# Sheet3.net
KiCad netlist of a schematic drawn in Altium Designer
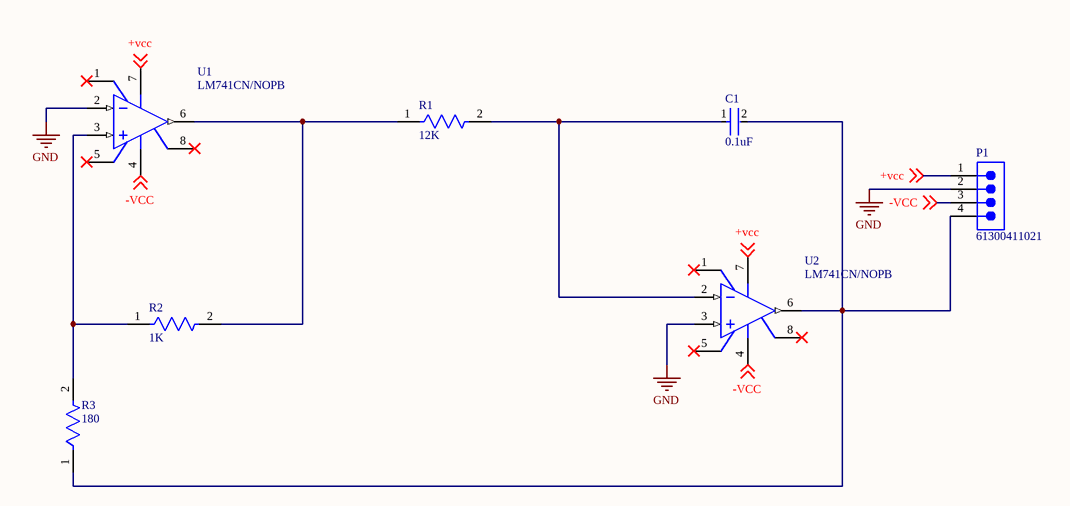
[diagram p0: Sheet3.SchDoc]

(export (version "E")
  (design (tool "Eeschema 10.0.6"))
  (components
    (comp (ref "C1")
      (value "0.1uF")
      (footprint "FP-RDE0M1-MFG")
      (description "Ceramic Capacitor 100nF ±10% 50V X7R Radial")
      (fields (field (name "TOLERANCE") "10%"))
      (libsource (lib "Altium Content Vault") (part "b4654b650e69147ec39a6b967a45e02"))
    )
    (comp (ref "P1")
      (value "61300411021")
      (footprint "61300411021")
      (libsource (lib "Altium Content Vault") (part "Header_Male_1R_04P"))
    )
    (comp (ref "R1")
      (value "12K")
      (footprint "FP-MRS25-MFG")
      (description "RES 1K OHM 0.6W 1% AXIAL")
      (fields (field (name "TOLERANCE") "1%"))
      (libsource (lib "Altium Content Vault") (part "1029c3af85768c4190bb7ad29bc67b5"))
    )
    (comp (ref "R2")
      (value "1K")
      (footprint "FP-MRS25-MFG")
      (description "RES 1K OHM 0.6W 1% AXIAL")
      (fields (field (name "TOLERANCE") "1%"))
      (libsource (lib "Altium Content Vault") (part "1029c3af85768c4190bb7ad29bc67b5"))
    )
    (comp (ref "R3")
      (value "180")
      (footprint "FP-MRS25-MFG")
      (description "RES 1K OHM 0.6W 1% AXIAL")
      (fields (field (name "TOLERANCE") "1%"))
      (libsource (lib "Altium Content Vault") (part "1029c3af85768c4190bb7ad29bc67b5"))
    )
    (comp (ref "U1")
      (value "LM741CN/NOPB")
      (footprint "P0008A")
      (description "Operational Amplifier, 8-pin MDIP, Pb-Free")
      (fields (field (name "MANUFACTURER") "Texas Instruments"))
      (libsource (lib "Altium Content Vault") (part "AMP-OPA-LM741-8"))
    )
    (comp (ref "U2")
      (value "LM741CN/NOPB")
      (footprint "P0008A")
      (description "Operational Amplifier, 8-pin MDIP, Pb-Free")
      (fields (field (name "MANUFACTURER") "Texas Instruments"))
      (libsource (lib "Altium Content Vault") (part "AMP-OPA-LM741-8"))
    )
  )
  (nets
    (net (code "1") (name "+vcc") (class "Default")
      (node (ref "P1") (pin "1") (pinfunction "1_1") (pintype "passive"))
      (node (ref "U1") (pin "7") (pinfunction "V+_7") (pintype "power_in"))
      (node (ref "U2") (pin "7") (pinfunction "V+_7") (pintype "power_in"))
    )
    (net (code "2") (name "-VCC") (class "Default")
      (node (ref "P1") (pin "3") (pinfunction "3_3") (pintype "passive"))
      (node (ref "U1") (pin "4") (pinfunction "V-_4") (pintype "power_in"))
      (node (ref "U2") (pin "4") (pinfunction "V-_4") (pintype "power_in"))
    )
    (net (code "3") (name "GND") (class "Default")
      (node (ref "P1") (pin "2") (pinfunction "2_2") (pintype "passive"))
      (node (ref "U1") (pin "2") (pinfunction "IN-_2") (pintype "input"))
      (node (ref "U2") (pin "3") (pinfunction "IN+_3") (pintype "input"))
    )
    (net (code "4") (name "Net-(U1-IN+)") (class "Default")
      (node (ref "R2") (pin "1") (pinfunction "1_1") (pintype "passive"))
      (node (ref "R3") (pin "2") (pinfunction "2_2") (pintype "passive"))
      (node (ref "U1") (pin "3") (pinfunction "IN+_3") (pintype "input"))
    )
    (net (code "5") (name "Net-(U1-OUT)") (class "Default")
      (node (ref "R1") (pin "1") (pinfunction "1_1") (pintype "passive"))
      (node (ref "R2") (pin "2") (pinfunction "2_2") (pintype "passive"))
      (node (ref "U1") (pin "6") (pinfunction "OUT_6") (pintype "output"))
    )
    (net (code "6") (name "Net-(U2-IN-)") (class "Default")
      (node (ref "C1") (pin "1") (pinfunction "1_1") (pintype "passive"))
      (node (ref "R1") (pin "2") (pinfunction "2_2") (pintype "passive"))
      (node (ref "U2") (pin "2") (pinfunction "IN-_2") (pintype "input"))
    )
    (net (code "7") (name "Net-(U2-OUT)") (class "Default")
      (node (ref "C1") (pin "2") (pinfunction "2_2") (pintype "passive"))
      (node (ref "P1") (pin "4") (pinfunction "4_4") (pintype "passive"))
      (node (ref "R3") (pin "1") (pinfunction "1_1") (pintype "passive"))
      (node (ref "U2") (pin "6") (pinfunction "OUT_6") (pintype "output"))
    )
    (net (code "8") (name "unconnected-(U1-NC-Pad8)") (class "Default")
      (node (ref "U1") (pin "8") (pinfunction "NC_8") (pintype "passive+no_connect"))
    )
    (net (code "9") (name "unconnected-(U1-OFS_NULL-Pad1)") (class "Default")
      (node (ref "U1") (pin "1") (pinfunction "OFS_NULL_1") (pintype "passive+no_connect"))
    )
    (net (code "10") (name "unconnected-(U1-OFS_NULL-Pad5)") (class "Default")
      (node (ref "U1") (pin "5") (pinfunction "OFS_NULL_5") (pintype "passive+no_connect"))
    )
    (net (code "11") (name "unconnected-(U2-NC-Pad8)") (class "Default")
      (node (ref "U2") (pin "8") (pinfunction "NC_8") (pintype "passive+no_connect"))
    )
    (net (code "12") (name "unconnected-(U2-OFS_NULL-Pad1)") (class "Default")
      (node (ref "U2") (pin "1") (pinfunction "OFS_NULL_1") (pintype "passive+no_connect"))
    )
    (net (code "13") (name "unconnected-(U2-OFS_NULL-Pad5)") (class "Default")
      (node (ref "U2") (pin "5") (pinfunction "OFS_NULL_5") (pintype "passive+no_connect"))
    )
  )
)
